# main_design2.net
KiCad netlist of a schematic drawn in EAGLE
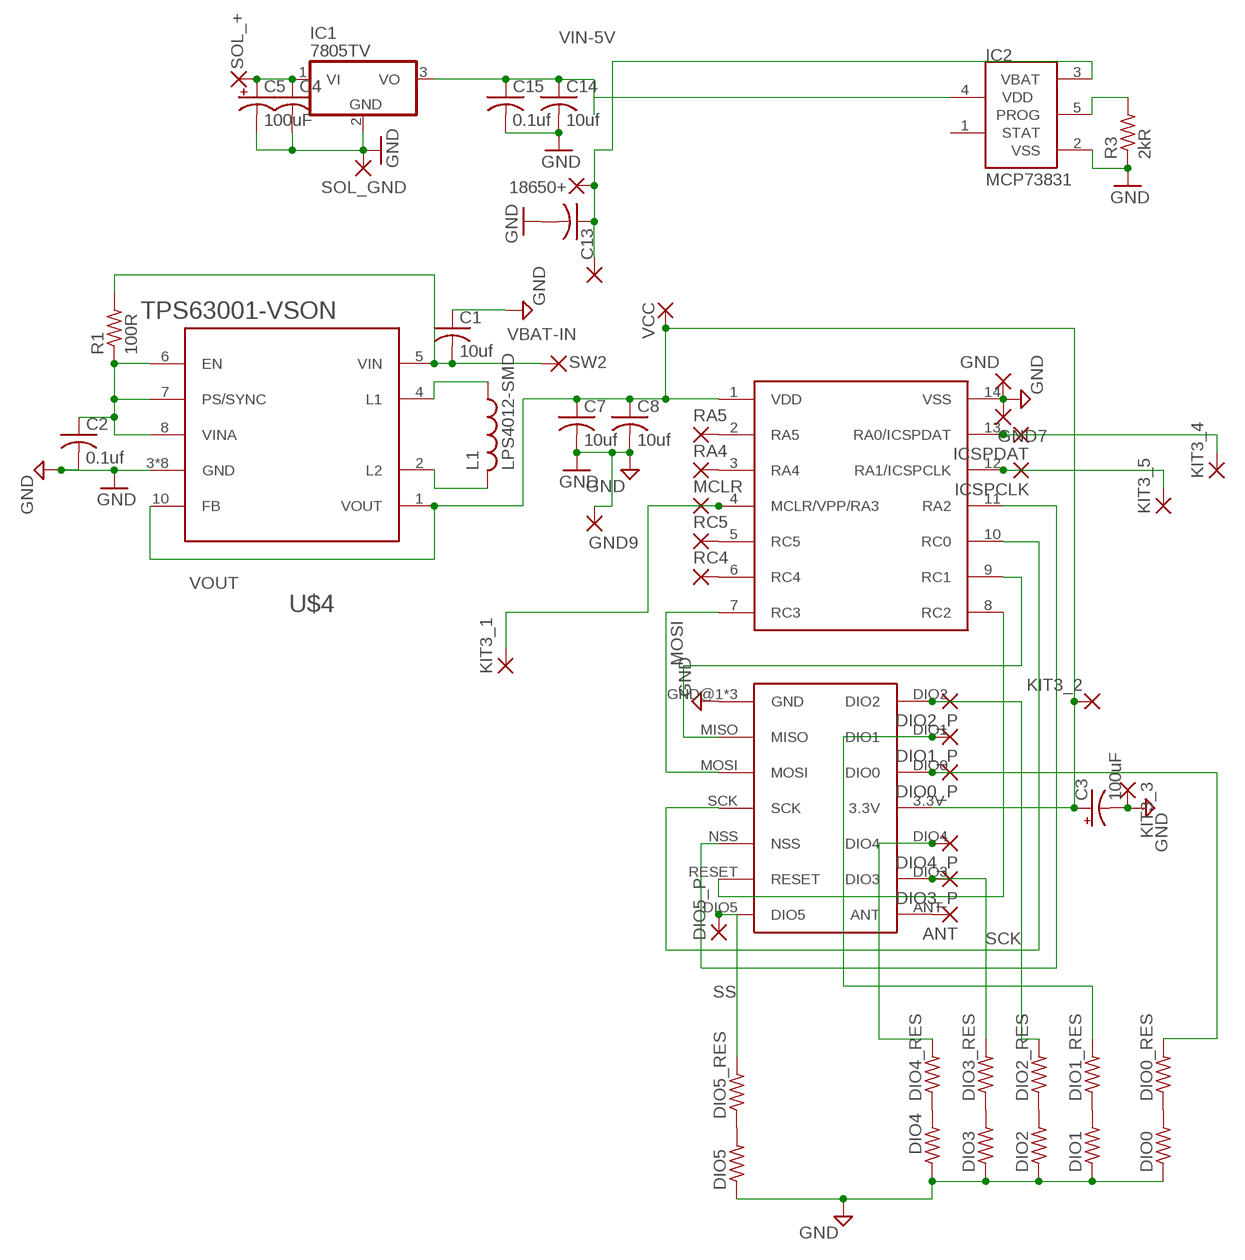
[diagram p0: schematic, sheet 1]

(export (version "E")
  (design (tool "Eeschema 10.0.6"))
  (components
    (comp (ref "18650+")
      (value "1,6/0,8")
      (footprint "eagle-import:1,6_0,8")
      (libsource (lib "eagle-import") (part "1,6/0,8"))
    )
    (comp (ref "ANT")
      (value "1,6/0,8")
      (footprint "eagle-import:1,6_0,8")
      (libsource (lib "eagle-import") (part "1,6/0,8"))
    )
    (comp (ref "C1")
      (value "10uf")
      (footprint "eagle-import:C0805")
      (libsource (lib "eagle-import") (part "C-USC0805"))
    )
    (comp (ref "C2")
      (value "0.1uf")
      (footprint "eagle-import:C0805")
      (libsource (lib "eagle-import") (part "C-USC0805"))
    )
    (comp (ref "C3")
      (value "100uF")
      (footprint "eagle-import:E5-5")
      (libsource (lib "eagle-import") (part "CPOL-USE5-5"))
    )
    (comp (ref "C4")
      (value "C-USC0402")
      (footprint "eagle-import:C0402")
      (libsource (lib "eagle-import") (part "C-USC0402"))
    )
    (comp (ref "C5")
      (value "100uF")
      (footprint "eagle-import:E5-6")
      (libsource (lib "eagle-import") (part "CPOL-USE5-6"))
    )
    (comp (ref "C7")
      (value "10uf")
      (footprint "eagle-import:C0805")
      (libsource (lib "eagle-import") (part "C-USC0805"))
    )
    (comp (ref "C8")
      (value "10uf")
      (footprint "eagle-import:C0805")
      (libsource (lib "eagle-import") (part "C-USC0805"))
    )
    (comp (ref "C13")
      (value "C-USC0805")
      (footprint "eagle-import:C0805")
      (libsource (lib "eagle-import") (part "C-USC0805"))
    )
    (comp (ref "C14")
      (value "10uf")
      (footprint "eagle-import:C0805")
      (libsource (lib "eagle-import") (part "C-USC0805"))
    )
    (comp (ref "C15")
      (value "0.1uf")
      (footprint "eagle-import:C0805")
      (libsource (lib "eagle-import") (part "C-USC0805"))
    )
    (comp (ref "DIO0")
      (value "R-US_R0805")
      (footprint "eagle-import:R0805")
      (libsource (lib "eagle-import") (part "R-US_R0805"))
    )
    (comp (ref "DIO0_P")
      (value "1,6/0,8")
      (footprint "eagle-import:1,6_0,8")
      (libsource (lib "eagle-import") (part "1,6/0,8"))
    )
    (comp (ref "DIO0_RES")
      (value "R-US_R0805")
      (footprint "eagle-import:R0805")
      (libsource (lib "eagle-import") (part "R-US_R0805"))
    )
    (comp (ref "DIO1")
      (value "R-US_R0805")
      (footprint "eagle-import:R0805")
      (libsource (lib "eagle-import") (part "R-US_R0805"))
    )
    (comp (ref "DIO1_P")
      (value "1,6/0,8")
      (footprint "eagle-import:1,6_0,8")
      (libsource (lib "eagle-import") (part "1,6/0,8"))
    )
    (comp (ref "DIO1_RES")
      (value "R-US_R0805")
      (footprint "eagle-import:R0805")
      (libsource (lib "eagle-import") (part "R-US_R0805"))
    )
    (comp (ref "DIO2")
      (value "R-US_R0805")
      (footprint "eagle-import:R0805")
      (libsource (lib "eagle-import") (part "R-US_R0805"))
    )
    (comp (ref "DIO2_P")
      (value "1,6/0,8")
      (footprint "eagle-import:1,6_0,8")
      (libsource (lib "eagle-import") (part "1,6/0,8"))
    )
    (comp (ref "DIO2_RES")
      (value "R-US_R0805")
      (footprint "eagle-import:R0805")
      (libsource (lib "eagle-import") (part "R-US_R0805"))
    )
    (comp (ref "DIO3")
      (value "R-US_R0805")
      (footprint "eagle-import:R0805")
      (libsource (lib "eagle-import") (part "R-US_R0805"))
    )
    (comp (ref "DIO3_P")
      (value "1,6/0,8")
      (footprint "eagle-import:1,6_0,8")
      (libsource (lib "eagle-import") (part "1,6/0,8"))
    )
    (comp (ref "DIO3_RES")
      (value "R-US_R0805")
      (footprint "eagle-import:R0805")
      (libsource (lib "eagle-import") (part "R-US_R0805"))
    )
    (comp (ref "DIO4")
      (value "R-US_R0805")
      (footprint "eagle-import:R0805")
      (libsource (lib "eagle-import") (part "R-US_R0805"))
    )
    (comp (ref "DIO4_P")
      (value "1,6/0,8")
      (footprint "eagle-import:1,6_0,8")
      (libsource (lib "eagle-import") (part "1,6/0,8"))
    )
    (comp (ref "DIO4_RES")
      (value "R-US_R0805")
      (footprint "eagle-import:R0805")
      (libsource (lib "eagle-import") (part "R-US_R0805"))
    )
    (comp (ref "DIO5")
      (value "R-US_R0805")
      (footprint "eagle-import:R0805")
      (libsource (lib "eagle-import") (part "R-US_R0805"))
    )
    (comp (ref "DIO5_P")
      (value "1,6/0,8")
      (footprint "eagle-import:1,6_0,8")
      (libsource (lib "eagle-import") (part "1,6/0,8"))
    )
    (comp (ref "DIO5_RES")
      (value "R-US_R0805")
      (footprint "eagle-import:R0805")
      (libsource (lib "eagle-import") (part "R-US_R0805"))
    )
    (comp (ref "GND")
      (value "1,6/0,8")
      (footprint "eagle-import:1,6_0,8")
      (libsource (lib "eagle-import") (part "1,6/0,8"))
    )
    (comp (ref "GND7")
      (value "1,6/0,8")
      (footprint "eagle-import:1,6_0,8")
      (libsource (lib "eagle-import") (part "1,6/0,8"))
    )
    (comp (ref "GND9")
      (value "1,6/0,8")
      (footprint "eagle-import:1,6_0,8")
      (libsource (lib "eagle-import") (part "1,6/0,8"))
    )
    (comp (ref "IC1")
      (value "7805TV")
      (footprint "eagle-import:TO220V")
      (libsource (lib "eagle-import") (part "78TV05"))
    )
    (comp (ref "IC2")
      (value "MCP73831")
      (footprint "eagle-import:SOT23-5L")
      (libsource (lib "eagle-import") (part "MCP73831"))
    )
    (comp (ref "ICSPCLK")
      (value "1,6/0,8")
      (footprint "eagle-import:1,6_0,8")
      (libsource (lib "eagle-import") (part "1,6/0,8"))
    )
    (comp (ref "ICSPDAT")
      (value "1,6/0,8")
      (footprint "eagle-import:1,6_0,8")
      (libsource (lib "eagle-import") (part "1,6/0,8"))
    )
    (comp (ref "KIT3_1")
      (value "1,6/0,8")
      (footprint "eagle-import:1,6_0,8")
      (libsource (lib "eagle-import") (part "1,6/0,8"))
    )
    (comp (ref "KIT3_2")
      (value "1,6/0,8")
      (footprint "eagle-import:1,6_0,8")
      (libsource (lib "eagle-import") (part "1,6/0,8"))
    )
    (comp (ref "KIT3_3")
      (value "1,6/0,8")
      (footprint "eagle-import:1,6_0,8")
      (libsource (lib "eagle-import") (part "1,6/0,8"))
    )
    (comp (ref "KIT3_4")
      (value "1,6/0,8")
      (footprint "eagle-import:1,6_0,8")
      (libsource (lib "eagle-import") (part "1,6/0,8"))
    )
    (comp (ref "KIT3_5")
      (value "1,6/0,8")
      (footprint "eagle-import:1,6_0,8")
      (libsource (lib "eagle-import") (part "1,6/0,8"))
    )
    (comp (ref "L1")
      (value "LPS4012-SMD")
      (footprint "eagle-import:LPS4012-222MRC")
      (libsource (lib "eagle-import") (part "LPS4012-SMD"))
    )
    (comp (ref "MCLR")
      (value "1,6/0,8")
      (footprint "eagle-import:1,6_0,8")
      (libsource (lib "eagle-import") (part "1,6/0,8"))
    )
    (comp (ref "R1")
      (value "100R")
      (footprint "eagle-import:R0805")
      (libsource (lib "eagle-import") (part "R-US_R0805"))
    )
    (comp (ref "R3")
      (value "2kR")
      (footprint "eagle-import:0204_7")
      (libsource (lib "eagle-import") (part "R-US_0204/7"))
    )
    (comp (ref "RA4")
      (value "1,6/0,8")
      (footprint "eagle-import:1,6_0,8")
      (libsource (lib "eagle-import") (part "1,6/0,8"))
    )
    (comp (ref "RA5")
      (value "1,6/0,8")
      (footprint "eagle-import:1,6_0,8")
      (libsource (lib "eagle-import") (part "1,6/0,8"))
    )
    (comp (ref "RC4")
      (value "1,6/0,8")
      (footprint "eagle-import:1,6_0,8")
      (libsource (lib "eagle-import") (part "1,6/0,8"))
    )
    (comp (ref "RC5")
      (value "1,6/0,8")
      (footprint "eagle-import:1,6_0,8")
      (libsource (lib "eagle-import") (part "1,6/0,8"))
    )
    (comp (ref "SOL_+")
      (value "1,6/0,8")
      (footprint "eagle-import:1,6_0,8")
      (libsource (lib "eagle-import") (part "1,6/0,8"))
    )
    (comp (ref "SOL_GND")
      (value "1,6/0,8")
      (footprint "eagle-import:1,6_0,8")
      (libsource (lib "eagle-import") (part "1,6/0,8"))
    )
    (comp (ref "SW1")
      (value "1,6/0,8")
      (footprint "eagle-import:1,6_0,8")
      (libsource (lib "eagle-import") (part "1,6/0,8"))
    )
    (comp (ref "SW2")
      (value "1,6/0,8")
      (footprint "eagle-import:1,6_0,8")
      (libsource (lib "eagle-import") (part "1,6/0,8"))
    )
    (comp (ref "U$1")
      (value "PIC16F1615-TSSOP")
      (footprint "eagle-import:PIC16F(L)1615-TSSOP")
      (libsource (lib "eagle-import") (part "PIC16F1615-TSSOP"))
    )
    (comp (ref "U$3")
      (value "RFM69HCW")
      (footprint "eagle-import:RFM69HCW")
      (libsource (lib "eagle-import") (part "RFM69HCW"))
    )
    (comp (ref "U$4")
      (value "TPS63001-VSON")
      (footprint "eagle-import:TPS63001-VSON")
      (libsource (lib "eagle-import") (part "TPS63001-VSON"))
    )
    (comp (ref "VCC")
      (value "VCC")
      (footprint "eagle-import:1,6_0,8")
      (libsource (lib "eagle-import") (part "1,6/0,8"))
    )
  )
  (nets
    (net (code "1") (name "/MOSI") (class "Default")
      (node (ref "U$1") (pin "7") (pinfunction "RC3_7") (pintype "bidirectional"))
      (node (ref "U$3") (pin "MOSI") (pinfunction "MOSI_MOSI") (pintype "bidirectional"))
    )
    (net (code "2") (name "/SCK") (class "Default")
      (node (ref "U$1") (pin "10") (pinfunction "RC0_10") (pintype "bidirectional"))
      (node (ref "U$3") (pin "SCK") (pinfunction "SCK_SCK") (pintype "bidirectional"))
    )
    (net (code "3") (name "/SS") (class "Default")
      (node (ref "U$1") (pin "11") (pinfunction "RA2_11") (pintype "bidirectional"))
      (node (ref "U$3") (pin "NSS") (pinfunction "NSS_NSS") (pintype "bidirectional"))
    )
    (net (code "4") (name "/VBAT-IN") (class "Default")
      (node (ref "C1") (pin "2") (pinfunction "2_2") (pintype "passive"))
      (node (ref "R1") (pin "2") (pinfunction "2_2") (pintype "passive"))
      (node (ref "SW2") (pin "1") (pinfunction "P_1") (pintype "passive"))
      (node (ref "U$4") (pin "5") (pinfunction "VIN_5") (pintype "bidirectional"))
    )
    (net (code "5") (name "/VIN-5V") (class "Default")
      (node (ref "C14") (pin "1") (pinfunction "1_1") (pintype "passive"))
      (node (ref "C15") (pin "1") (pinfunction "1_1") (pintype "passive"))
      (node (ref "IC1") (pin "3") (pinfunction "VO_3") (pintype "passive"))
      (node (ref "IC2") (pin "4") (pinfunction "VDD_4") (pintype "bidirectional"))
    )
    (net (code "6") (name "/VOUT") (class "Default")
      (node (ref "C3") (pin "+") (pinfunction "+_+") (pintype "passive"))
      (node (ref "C7") (pin "1") (pinfunction "1_1") (pintype "passive"))
      (node (ref "C8") (pin "1") (pinfunction "1_1") (pintype "passive"))
      (node (ref "KIT3_2") (pin "1") (pinfunction "P_1") (pintype "passive"))
      (node (ref "U$1") (pin "1") (pinfunction "VDD_1") (pintype "bidirectional"))
      (node (ref "U$3") (pin "3.3V") (pinfunction "3.3V_3.3V") (pintype "bidirectional"))
      (node (ref "U$4") (pin "1") (pinfunction "VOUT_1") (pintype "bidirectional"))
      (node (ref "U$4") (pin "10") (pinfunction "FB_10") (pintype "bidirectional"))
      (node (ref "VCC") (pin "1") (pinfunction "P_1") (pintype "passive"))
    )
    (net (code "7") (name "GND") (class "Default")
      (node (ref "C1") (pin "1") (pinfunction "1_1") (pintype "passive"))
      (node (ref "C13") (pin "2") (pinfunction "2_2") (pintype "passive"))
      (node (ref "C14") (pin "2") (pinfunction "2_2") (pintype "passive"))
      (node (ref "C15") (pin "2") (pinfunction "2_2") (pintype "passive"))
      (node (ref "C2") (pin "2") (pinfunction "2_2") (pintype "passive"))
      (node (ref "C3") (pin "-") (pinfunction "-_-") (pintype "passive"))
      (node (ref "C4") (pin "2") (pinfunction "2_2") (pintype "passive"))
      (node (ref "C5") (pin "-") (pinfunction "-_-") (pintype "passive"))
      (node (ref "C7") (pin "2") (pinfunction "2_2") (pintype "passive"))
      (node (ref "C8") (pin "2") (pinfunction "2_2") (pintype "passive"))
      (node (ref "DIO0") (pin "1") (pinfunction "1_1") (pintype "passive"))
      (node (ref "DIO1") (pin "1") (pinfunction "1_1") (pintype "passive"))
      (node (ref "DIO2") (pin "1") (pinfunction "1_1") (pintype "passive"))
      (node (ref "DIO3") (pin "1") (pinfunction "1_1") (pintype "passive"))
      (node (ref "DIO4") (pin "1") (pinfunction "1_1") (pintype "passive"))
      (node (ref "DIO5") (pin "1") (pinfunction "1_1") (pintype "passive"))
      (node (ref "GND") (pin "1") (pinfunction "P_1") (pintype "passive"))
      (node (ref "GND7") (pin "1") (pinfunction "P_1") (pintype "passive"))
      (node (ref "GND9") (pin "1") (pinfunction "P_1") (pintype "passive"))
      (node (ref "IC1") (pin "2") (pinfunction "GND_2") (pintype "passive"))
      (node (ref "IC2") (pin "2") (pinfunction "VSS_2") (pintype "bidirectional"))
      (node (ref "KIT3_3") (pin "1") (pinfunction "P_1") (pintype "passive"))
      (node (ref "R3") (pin "1") (pinfunction "1_1") (pintype "passive"))
      (node (ref "SOL_GND") (pin "1") (pinfunction "P_1") (pintype "passive"))
      (node (ref "U$1") (pin "14") (pinfunction "VSS_14") (pintype "bidirectional"))
      (node (ref "U$3") (pin "GND@1") (pinfunction "GND_GND@1") (pintype "bidirectional"))
      (node (ref "U$3") (pin "GND@2") (pinfunction "GND_GND@2") (pintype "bidirectional"))
      (node (ref "U$3") (pin "GND@3") (pinfunction "GND_GND@3") (pintype "bidirectional"))
      (node (ref "U$4") (pin "11@0") (pinfunction "GND_11@0") (pintype "bidirectional"))
      (node (ref "U$4") (pin "11@1") (pinfunction "GND_11@1") (pintype "bidirectional"))
      (node (ref "U$4") (pin "11@2") (pinfunction "GND_11@2") (pintype "bidirectional"))
      (node (ref "U$4") (pin "11@3") (pinfunction "GND_11@3") (pintype "bidirectional"))
      (node (ref "U$4") (pin "11@4") (pinfunction "GND_11@4") (pintype "bidirectional"))
      (node (ref "U$4") (pin "11@5") (pinfunction "GND_11@5") (pintype "bidirectional"))
      (node (ref "U$4") (pin "3") (pinfunction "GND_3") (pintype "bidirectional"))
      (node (ref "U$4") (pin "9") (pinfunction "GND_9") (pintype "bidirectional"))
    )
    (net (code "8") (name "Net-(18650+-P)") (class "Default")
      (node (ref "18650+") (pin "1") (pinfunction "P_1") (pintype "passive"))
      (node (ref "C13") (pin "1") (pinfunction "1_1") (pintype "passive"))
      (node (ref "IC2") (pin "3") (pinfunction "VBAT_3") (pintype "bidirectional"))
      (node (ref "SW1") (pin "1") (pinfunction "P_1") (pintype "passive"))
    )
    (net (code "9") (name "Net-(ANT-P)") (class "Default")
      (node (ref "ANT") (pin "1") (pinfunction "P_1") (pintype "passive"))
      (node (ref "U$3") (pin "ANT") (pinfunction "ANT_ANT") (pintype "bidirectional"))
    )
    (net (code "10") (name "Net-(DIO0-Pad2)") (class "Default")
      (node (ref "DIO0") (pin "2") (pinfunction "2_2") (pintype "passive"))
      (node (ref "DIO0_RES") (pin "1") (pinfunction "1_1") (pintype "passive"))
    )
    (net (code "11") (name "Net-(DIO0_P-P)") (class "Default")
      (node (ref "DIO0_P") (pin "1") (pinfunction "P_1") (pintype "passive"))
      (node (ref "DIO0_RES") (pin "2") (pinfunction "2_2") (pintype "passive"))
      (node (ref "U$3") (pin "DIO0") (pinfunction "DIO0_DIO0") (pintype "bidirectional"))
    )
    (net (code "12") (name "Net-(DIO1-Pad2)") (class "Default")
      (node (ref "DIO1") (pin "2") (pinfunction "2_2") (pintype "passive"))
      (node (ref "DIO1_RES") (pin "1") (pinfunction "1_1") (pintype "passive"))
    )
    (net (code "13") (name "Net-(DIO1_P-P)") (class "Default")
      (node (ref "DIO1_P") (pin "1") (pinfunction "P_1") (pintype "passive"))
      (node (ref "DIO1_RES") (pin "2") (pinfunction "2_2") (pintype "passive"))
      (node (ref "U$3") (pin "DIO1") (pinfunction "DIO1_DIO1") (pintype "bidirectional"))
    )
    (net (code "14") (name "Net-(DIO2-Pad2)") (class "Default")
      (node (ref "DIO2") (pin "2") (pinfunction "2_2") (pintype "passive"))
      (node (ref "DIO2_RES") (pin "1") (pinfunction "1_1") (pintype "passive"))
    )
    (net (code "15") (name "Net-(DIO2_P-P)") (class "Default")
      (node (ref "DIO2_P") (pin "1") (pinfunction "P_1") (pintype "passive"))
      (node (ref "DIO2_RES") (pin "2") (pinfunction "2_2") (pintype "passive"))
      (node (ref "U$3") (pin "DIO2") (pinfunction "DIO2_DIO2") (pintype "bidirectional"))
    )
    (net (code "16") (name "Net-(DIO3-Pad2)") (class "Default")
      (node (ref "DIO3") (pin "2") (pinfunction "2_2") (pintype "passive"))
      (node (ref "DIO3_RES") (pin "1") (pinfunction "1_1") (pintype "passive"))
    )
    (net (code "17") (name "Net-(DIO3_P-P)") (class "Default")
      (node (ref "DIO3_P") (pin "1") (pinfunction "P_1") (pintype "passive"))
      (node (ref "DIO3_RES") (pin "2") (pinfunction "2_2") (pintype "passive"))
      (node (ref "U$3") (pin "DIO3") (pinfunction "DIO3_DIO3") (pintype "bidirectional"))
    )
    (net (code "18") (name "Net-(DIO4-Pad2)") (class "Default")
      (node (ref "DIO4") (pin "2") (pinfunction "2_2") (pintype "passive"))
      (node (ref "DIO4_RES") (pin "1") (pinfunction "1_1") (pintype "passive"))
    )
    (net (code "19") (name "Net-(DIO4_P-P)") (class "Default")
      (node (ref "DIO4_P") (pin "1") (pinfunction "P_1") (pintype "passive"))
      (node (ref "DIO4_RES") (pin "2") (pinfunction "2_2") (pintype "passive"))
      (node (ref "U$3") (pin "DIO4") (pinfunction "DIO4_DIO4") (pintype "bidirectional"))
    )
    (net (code "20") (name "Net-(DIO5-Pad2)") (class "Default")
      (node (ref "DIO5") (pin "2") (pinfunction "2_2") (pintype "passive"))
      (node (ref "DIO5_RES") (pin "1") (pinfunction "1_1") (pintype "passive"))
    )
    (net (code "21") (name "Net-(DIO5_P-P)") (class "Default")
      (node (ref "DIO5_P") (pin "1") (pinfunction "P_1") (pintype "passive"))
      (node (ref "DIO5_RES") (pin "2") (pinfunction "2_2") (pintype "passive"))
      (node (ref "U$3") (pin "DIO5") (pinfunction "DIO5_DIO5") (pintype "bidirectional"))
    )
    (net (code "22") (name "Net-(IC1-VI)") (class "Default")
      (node (ref "C4") (pin "1") (pinfunction "1_1") (pintype "passive"))
      (node (ref "C5") (pin "+") (pinfunction "+_+") (pintype "passive"))
      (node (ref "IC1") (pin "1") (pinfunction "VI_1") (pintype "input"))
      (node (ref "SOL_+") (pin "1") (pinfunction "P_1") (pintype "passive"))
    )
    (net (code "23") (name "Net-(IC2-PROG)") (class "Default")
      (node (ref "IC2") (pin "5") (pinfunction "PROG_5") (pintype "bidirectional"))
      (node (ref "R3") (pin "2") (pinfunction "2_2") (pintype "passive"))
    )
    (net (code "24") (name "Net-(ICSPCLK-P)") (class "Default")
      (node (ref "ICSPCLK") (pin "1") (pinfunction "P_1") (pintype "passive"))
      (node (ref "KIT3_5") (pin "1") (pinfunction "P_1") (pintype "passive"))
      (node (ref "U$1") (pin "12") (pinfunction "RA1/ICSPCLK_12") (pintype "bidirectional"))
    )
    (net (code "25") (name "Net-(ICSPDAT-P)") (class "Default")
      (node (ref "ICSPDAT") (pin "1") (pinfunction "P_1") (pintype "passive"))
      (node (ref "KIT3_4") (pin "1") (pinfunction "P_1") (pintype "passive"))
      (node (ref "U$1") (pin "13") (pinfunction "RA0/ICSPDAT_13") (pintype "bidirectional"))
    )
    (net (code "26") (name "Net-(KIT3_1-P)") (class "Default")
      (node (ref "KIT3_1") (pin "1") (pinfunction "P_1") (pintype "passive"))
      (node (ref "MCLR") (pin "1") (pinfunction "P_1") (pintype "passive"))
      (node (ref "U$1") (pin "4") (pinfunction "MCLR/VPP/RA3_4") (pintype "bidirectional"))
    )
    (net (code "27") (name "Net-(L1-1)") (class "Default")
      (node (ref "L1") (pin "P$1") (pinfunction "1_P$1") (pintype "passive"))
      (node (ref "U$4") (pin "4") (pinfunction "L1_4") (pintype "bidirectional"))
    )
    (net (code "28") (name "Net-(L1-2)") (class "Default")
      (node (ref "L1") (pin "P$2") (pinfunction "2_P$2") (pintype "passive"))
      (node (ref "U$4") (pin "2") (pinfunction "L2_2") (pintype "bidirectional"))
    )
    (net (code "29") (name "Net-(RA4-P)") (class "Default")
      (node (ref "RA4") (pin "1") (pinfunction "P_1") (pintype "passive"))
      (node (ref "U$1") (pin "3") (pinfunction "RA4_3") (pintype "bidirectional"))
    )
    (net (code "30") (name "Net-(RA5-P)") (class "Default")
      (node (ref "RA5") (pin "1") (pinfunction "P_1") (pintype "passive"))
      (node (ref "U$1") (pin "2") (pinfunction "RA5_2") (pintype "bidirectional"))
    )
    (net (code "31") (name "Net-(RC4-P)") (class "Default")
      (node (ref "RC4") (pin "1") (pinfunction "P_1") (pintype "passive"))
      (node (ref "U$1") (pin "6") (pinfunction "RC4_6") (pintype "bidirectional"))
    )
    (net (code "32") (name "Net-(RC5-P)") (class "Default")
      (node (ref "RC5") (pin "1") (pinfunction "P_1") (pintype "passive"))
      (node (ref "U$1") (pin "5") (pinfunction "RC5_5") (pintype "bidirectional"))
    )
    (net (code "33") (name "Net-(U$1-RC1)") (class "Default")
      (node (ref "U$1") (pin "9") (pinfunction "RC1_9") (pintype "bidirectional"))
      (node (ref "U$3") (pin "MISO") (pinfunction "MISO_MISO") (pintype "bidirectional"))
    )
    (net (code "34") (name "Net-(U$1-RC2)") (class "Default")
      (node (ref "U$1") (pin "8") (pinfunction "RC2_8") (pintype "bidirectional"))
      (node (ref "U$3") (pin "RESET") (pinfunction "RESET_RESET") (pintype "bidirectional"))
    )
    (net (code "35") (name "Net-(U$4-EN)") (class "Default")
      (node (ref "C2") (pin "1") (pinfunction "1_1") (pintype "passive"))
      (node (ref "R1") (pin "1") (pinfunction "1_1") (pintype "passive"))
      (node (ref "U$4") (pin "6") (pinfunction "EN_6") (pintype "bidirectional"))
      (node (ref "U$4") (pin "7") (pinfunction "PS/SYNC_7") (pintype "bidirectional"))
      (node (ref "U$4") (pin "8") (pinfunction "VINA_8") (pintype "bidirectional"))
    )
    (net (code "36") (name "unconnected-(IC2-STAT-Pad1)") (class "Default")
      (node (ref "IC2") (pin "1") (pinfunction "STAT_1") (pintype "bidirectional"))
    )
  )
)
